# 1705-Servo2.net
KiCad netlist of a schematic drawn in EAGLE
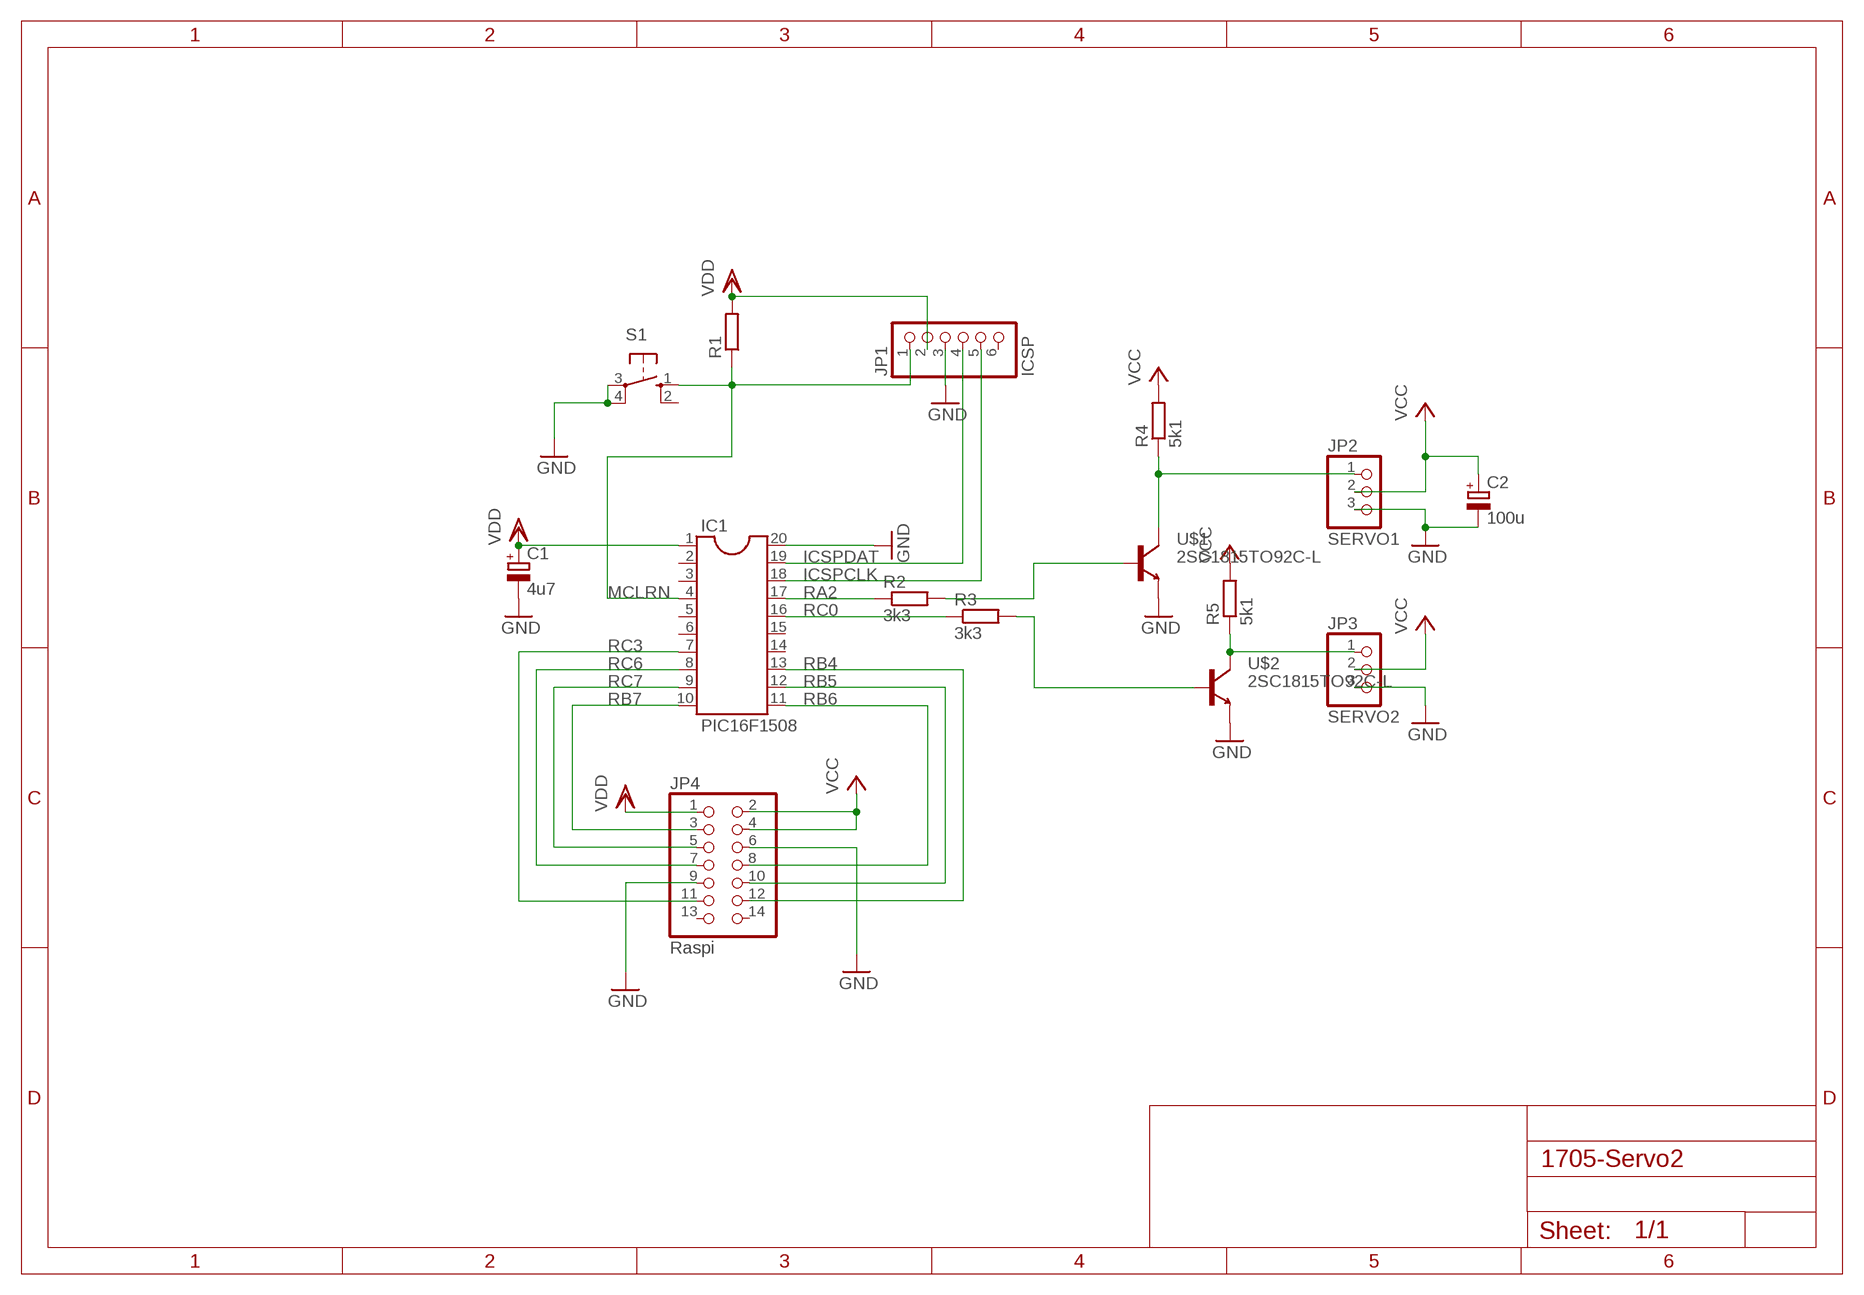
[diagram p0: schematic, sheet 1]

(export (version "E")
  (design (tool "Eeschema 10.0.6"))
  (components
    (comp (ref "C1")
      (value "4u7")
      (footprint "eagle-import:E5-6E")
      (libsource (lib "eagle-import") (part "CPOL-EUE5-6E"))
    )
    (comp (ref "C2")
      (value "100u")
      (footprint "eagle-import:E2,5-6E")
      (libsource (lib "eagle-import") (part "CPOL-EUE2.5-6E"))
    )
    (comp (ref "IC1")
      (value "PIC16F1508")
      (footprint "eagle-import:DIL20")
      (libsource (lib "eagle-import") (part "DIL20"))
    )
    (comp (ref "JP1")
      (value "ICSP")
      (footprint "eagle-import:1X06")
      (libsource (lib "eagle-import") (part "PINHD-1X6"))
    )
    (comp (ref "JP2")
      (value "SERVO1")
      (footprint "eagle-import:1X03")
      (libsource (lib "eagle-import") (part "PINHD-1X3"))
    )
    (comp (ref "JP3")
      (value "SERVO2")
      (footprint "eagle-import:1X03")
      (libsource (lib "eagle-import") (part "PINHD-1X3"))
    )
    (comp (ref "JP4")
      (value "Raspi")
      (footprint "eagle-import:2X07")
      (libsource (lib "eagle-import") (part "PINHD-2X7"))
    )
    (comp (ref "R1")
      (value "R-EU_0207/2V")
      (footprint "eagle-import:0207_2V")
      (libsource (lib "eagle-import") (part "R-EU_0207/2V"))
    )
    (comp (ref "R2")
      (value "3k3")
      (footprint "eagle-import:0204_8")
      (libsource (lib "eagle-import") (part "R-EU_0204/8"))
    )
    (comp (ref "R3")
      (value "3k3")
      (footprint "eagle-import:0204_8")
      (libsource (lib "eagle-import") (part "R-EU_0204/8"))
    )
    (comp (ref "R4")
      (value "5k1")
      (footprint "eagle-import:0207_2V")
      (libsource (lib "eagle-import") (part "R-EU_0207/2V"))
    )
    (comp (ref "R5")
      (value "5k1")
      (footprint "eagle-import:0207_2V")
      (libsource (lib "eagle-import") (part "R-EU_0207/2V"))
    )
    (comp (ref "S1")
      (value "10-XX")
      (footprint "eagle-import:B3F-10XX")
      (fields (field (name "MPN") "B3F-1000"))
      (libsource (lib "eagle-import") (part "10-XX"))
    )
    (comp (ref "U$1")
      (value "2SC1815TO92C-L")
      (footprint "eagle-import:TO92C-L")
      (libsource (lib "eagle-import") (part "2SC1815TO92C-L"))
    )
    (comp (ref "U$2")
      (value "2SC1815TO92C-L")
      (footprint "eagle-import:TO92C-L")
      (libsource (lib "eagle-import") (part "2SC1815TO92C-L"))
    )
  )
  (nets
    (net (code "1") (name "/ICSPCLK") (class "Default")
      (node (ref "IC1") (pin "18") (pinfunction "18_18") (pintype "passive"))
      (node (ref "JP1") (pin "5") (pinfunction "5_5") (pintype "passive"))
    )
    (net (code "2") (name "/ICSPDAT") (class "Default")
      (node (ref "IC1") (pin "19") (pinfunction "19_19") (pintype "passive"))
      (node (ref "JP1") (pin "4") (pinfunction "4_4") (pintype "passive"))
    )
    (net (code "3") (name "/MCLRN") (class "Default")
      (node (ref "IC1") (pin "4") (pinfunction "4_4") (pintype "passive"))
      (node (ref "JP1") (pin "1") (pinfunction "1_1") (pintype "passive"))
      (node (ref "R1") (pin "1") (pinfunction "1_1") (pintype "passive"))
      (node (ref "S1") (pin "1") (pinfunction "S_1") (pintype "passive"))
    )
    (net (code "4") (name "/RA2") (class "Default")
      (node (ref "IC1") (pin "17") (pinfunction "17_17") (pintype "passive"))
      (node (ref "R2") (pin "1") (pinfunction "1_1") (pintype "passive"))
    )
    (net (code "5") (name "/RB4") (class "Default")
      (node (ref "IC1") (pin "13") (pinfunction "13_13") (pintype "passive"))
      (node (ref "JP4") (pin "12") (pinfunction "12_12") (pintype "passive"))
    )
    (net (code "6") (name "/RB5") (class "Default")
      (node (ref "IC1") (pin "12") (pinfunction "12_12") (pintype "passive"))
      (node (ref "JP4") (pin "10") (pinfunction "10_10") (pintype "passive"))
    )
    (net (code "7") (name "/RB6") (class "Default")
      (node (ref "IC1") (pin "11") (pinfunction "11_11") (pintype "passive"))
      (node (ref "JP4") (pin "8") (pinfunction "8_8") (pintype "passive"))
    )
    (net (code "8") (name "/RB7") (class "Default")
      (node (ref "IC1") (pin "10") (pinfunction "10_10") (pintype "passive"))
      (node (ref "JP4") (pin "3") (pinfunction "3_3") (pintype "passive"))
    )
    (net (code "9") (name "/RC0") (class "Default")
      (node (ref "IC1") (pin "16") (pinfunction "16_16") (pintype "passive"))
      (node (ref "R3") (pin "1") (pinfunction "1_1") (pintype "passive"))
    )
    (net (code "10") (name "/RC3") (class "Default")
      (node (ref "IC1") (pin "7") (pinfunction "7_7") (pintype "passive"))
      (node (ref "JP4") (pin "11") (pinfunction "11_11") (pintype "passive"))
    )
    (net (code "11") (name "/RC6") (class "Default")
      (node (ref "IC1") (pin "8") (pinfunction "8_8") (pintype "passive"))
      (node (ref "JP4") (pin "7") (pinfunction "7_7") (pintype "passive"))
    )
    (net (code "12") (name "/RC7") (class "Default")
      (node (ref "IC1") (pin "9") (pinfunction "9_9") (pintype "passive"))
      (node (ref "JP4") (pin "5") (pinfunction "5_5") (pintype "passive"))
    )
    (net (code "13") (name "GND") (class "Default")
      (node (ref "C1") (pin "-") (pinfunction "-_-") (pintype "passive"))
      (node (ref "C2") (pin "-") (pinfunction "-_-") (pintype "passive"))
      (node (ref "IC1") (pin "20") (pinfunction "20_20") (pintype "passive"))
      (node (ref "JP1") (pin "3") (pinfunction "3_3") (pintype "passive"))
      (node (ref "JP2") (pin "3") (pinfunction "3_3") (pintype "passive"))
      (node (ref "JP3") (pin "3") (pinfunction "3_3") (pintype "passive"))
      (node (ref "JP4") (pin "6") (pinfunction "6_6") (pintype "passive"))
      (node (ref "JP4") (pin "9") (pinfunction "9_9") (pintype "passive"))
      (node (ref "S1") (pin "3") (pinfunction "P_3") (pintype "passive"))
      (node (ref "S1") (pin "4") (pinfunction "P1_4") (pintype "passive"))
      (node (ref "U$1") (pin "1") (pinfunction "E_1") (pintype "passive"))
      (node (ref "U$2") (pin "1") (pinfunction "E_1") (pintype "passive"))
    )
    (net (code "14") (name "Net-(U$1-B)") (class "Default")
      (node (ref "R2") (pin "2") (pinfunction "2_2") (pintype "passive"))
      (node (ref "U$1") (pin "3") (pinfunction "B_3") (pintype "passive"))
    )
    (net (code "15") (name "Net-(U$1-C)") (class "Default")
      (node (ref "JP2") (pin "1") (pinfunction "1_1") (pintype "passive"))
      (node (ref "R4") (pin "1") (pinfunction "1_1") (pintype "passive"))
      (node (ref "U$1") (pin "2") (pinfunction "C_2") (pintype "passive"))
    )
    (net (code "16") (name "Net-(U$2-B)") (class "Default")
      (node (ref "R3") (pin "2") (pinfunction "2_2") (pintype "passive"))
      (node (ref "U$2") (pin "3") (pinfunction "B_3") (pintype "passive"))
    )
    (net (code "17") (name "Net-(U$2-C)") (class "Default")
      (node (ref "JP3") (pin "1") (pinfunction "1_1") (pintype "passive"))
      (node (ref "R5") (pin "1") (pinfunction "1_1") (pintype "passive"))
      (node (ref "U$2") (pin "2") (pinfunction "C_2") (pintype "passive"))
    )
    (net (code "18") (name "VCC") (class "Default")
      (node (ref "C2") (pin "+") (pinfunction "+_+") (pintype "passive"))
      (node (ref "JP2") (pin "2") (pinfunction "2_2") (pintype "passive"))
      (node (ref "JP3") (pin "2") (pinfunction "2_2") (pintype "passive"))
      (node (ref "JP4") (pin "2") (pinfunction "2_2") (pintype "passive"))
      (node (ref "JP4") (pin "4") (pinfunction "4_4") (pintype "passive"))
      (node (ref "R4") (pin "2") (pinfunction "2_2") (pintype "passive"))
      (node (ref "R5") (pin "2") (pinfunction "2_2") (pintype "passive"))
    )
    (net (code "19") (name "VDD") (class "Default")
      (node (ref "C1") (pin "+") (pinfunction "+_+") (pintype "passive"))
      (node (ref "IC1") (pin "1") (pinfunction "1_1") (pintype "passive"))
      (node (ref "JP1") (pin "2") (pinfunction "2_2") (pintype "passive"))
      (node (ref "JP4") (pin "1") (pinfunction "1_1") (pintype "passive"))
      (node (ref "R1") (pin "2") (pinfunction "2_2") (pintype "passive"))
    )
    (net (code "20") (name "unconnected-(IC1-Pad2)") (class "Default")
      (node (ref "IC1") (pin "2") (pinfunction "2_2") (pintype "passive"))
    )
    (net (code "21") (name "unconnected-(IC1-Pad3)") (class "Default")
      (node (ref "IC1") (pin "3") (pinfunction "3_3") (pintype "passive"))
    )
    (net (code "22") (name "unconnected-(IC1-Pad5)") (class "Default")
      (node (ref "IC1") (pin "5") (pinfunction "5_5") (pintype "passive"))
    )
    (net (code "23") (name "unconnected-(IC1-Pad6)") (class "Default")
      (node (ref "IC1") (pin "6") (pinfunction "6_6") (pintype "passive"))
    )
    (net (code "24") (name "unconnected-(IC1-Pad14)") (class "Default")
      (node (ref "IC1") (pin "14") (pinfunction "14_14") (pintype "passive"))
    )
    (net (code "25") (name "unconnected-(IC1-Pad15)") (class "Default")
      (node (ref "IC1") (pin "15") (pinfunction "15_15") (pintype "passive"))
    )
    (net (code "26") (name "unconnected-(JP1-Pad6)") (class "Default")
      (node (ref "JP1") (pin "6") (pinfunction "6_6") (pintype "passive"))
    )
    (net (code "27") (name "unconnected-(JP4-Pad13)") (class "Default")
      (node (ref "JP4") (pin "13") (pinfunction "13_13") (pintype "passive"))
    )
    (net (code "28") (name "unconnected-(JP4-Pad14)") (class "Default")
      (node (ref "JP4") (pin "14") (pinfunction "14_14") (pintype "passive"))
    )
    (net (code "29") (name "unconnected-(S1-S1-Pad2)") (class "Default")
      (node (ref "S1") (pin "2") (pinfunction "S1_2") (pintype "passive"))
    )
  )
)
